# power.net
KiCad netlist of a schematic drawn in Altium Designer
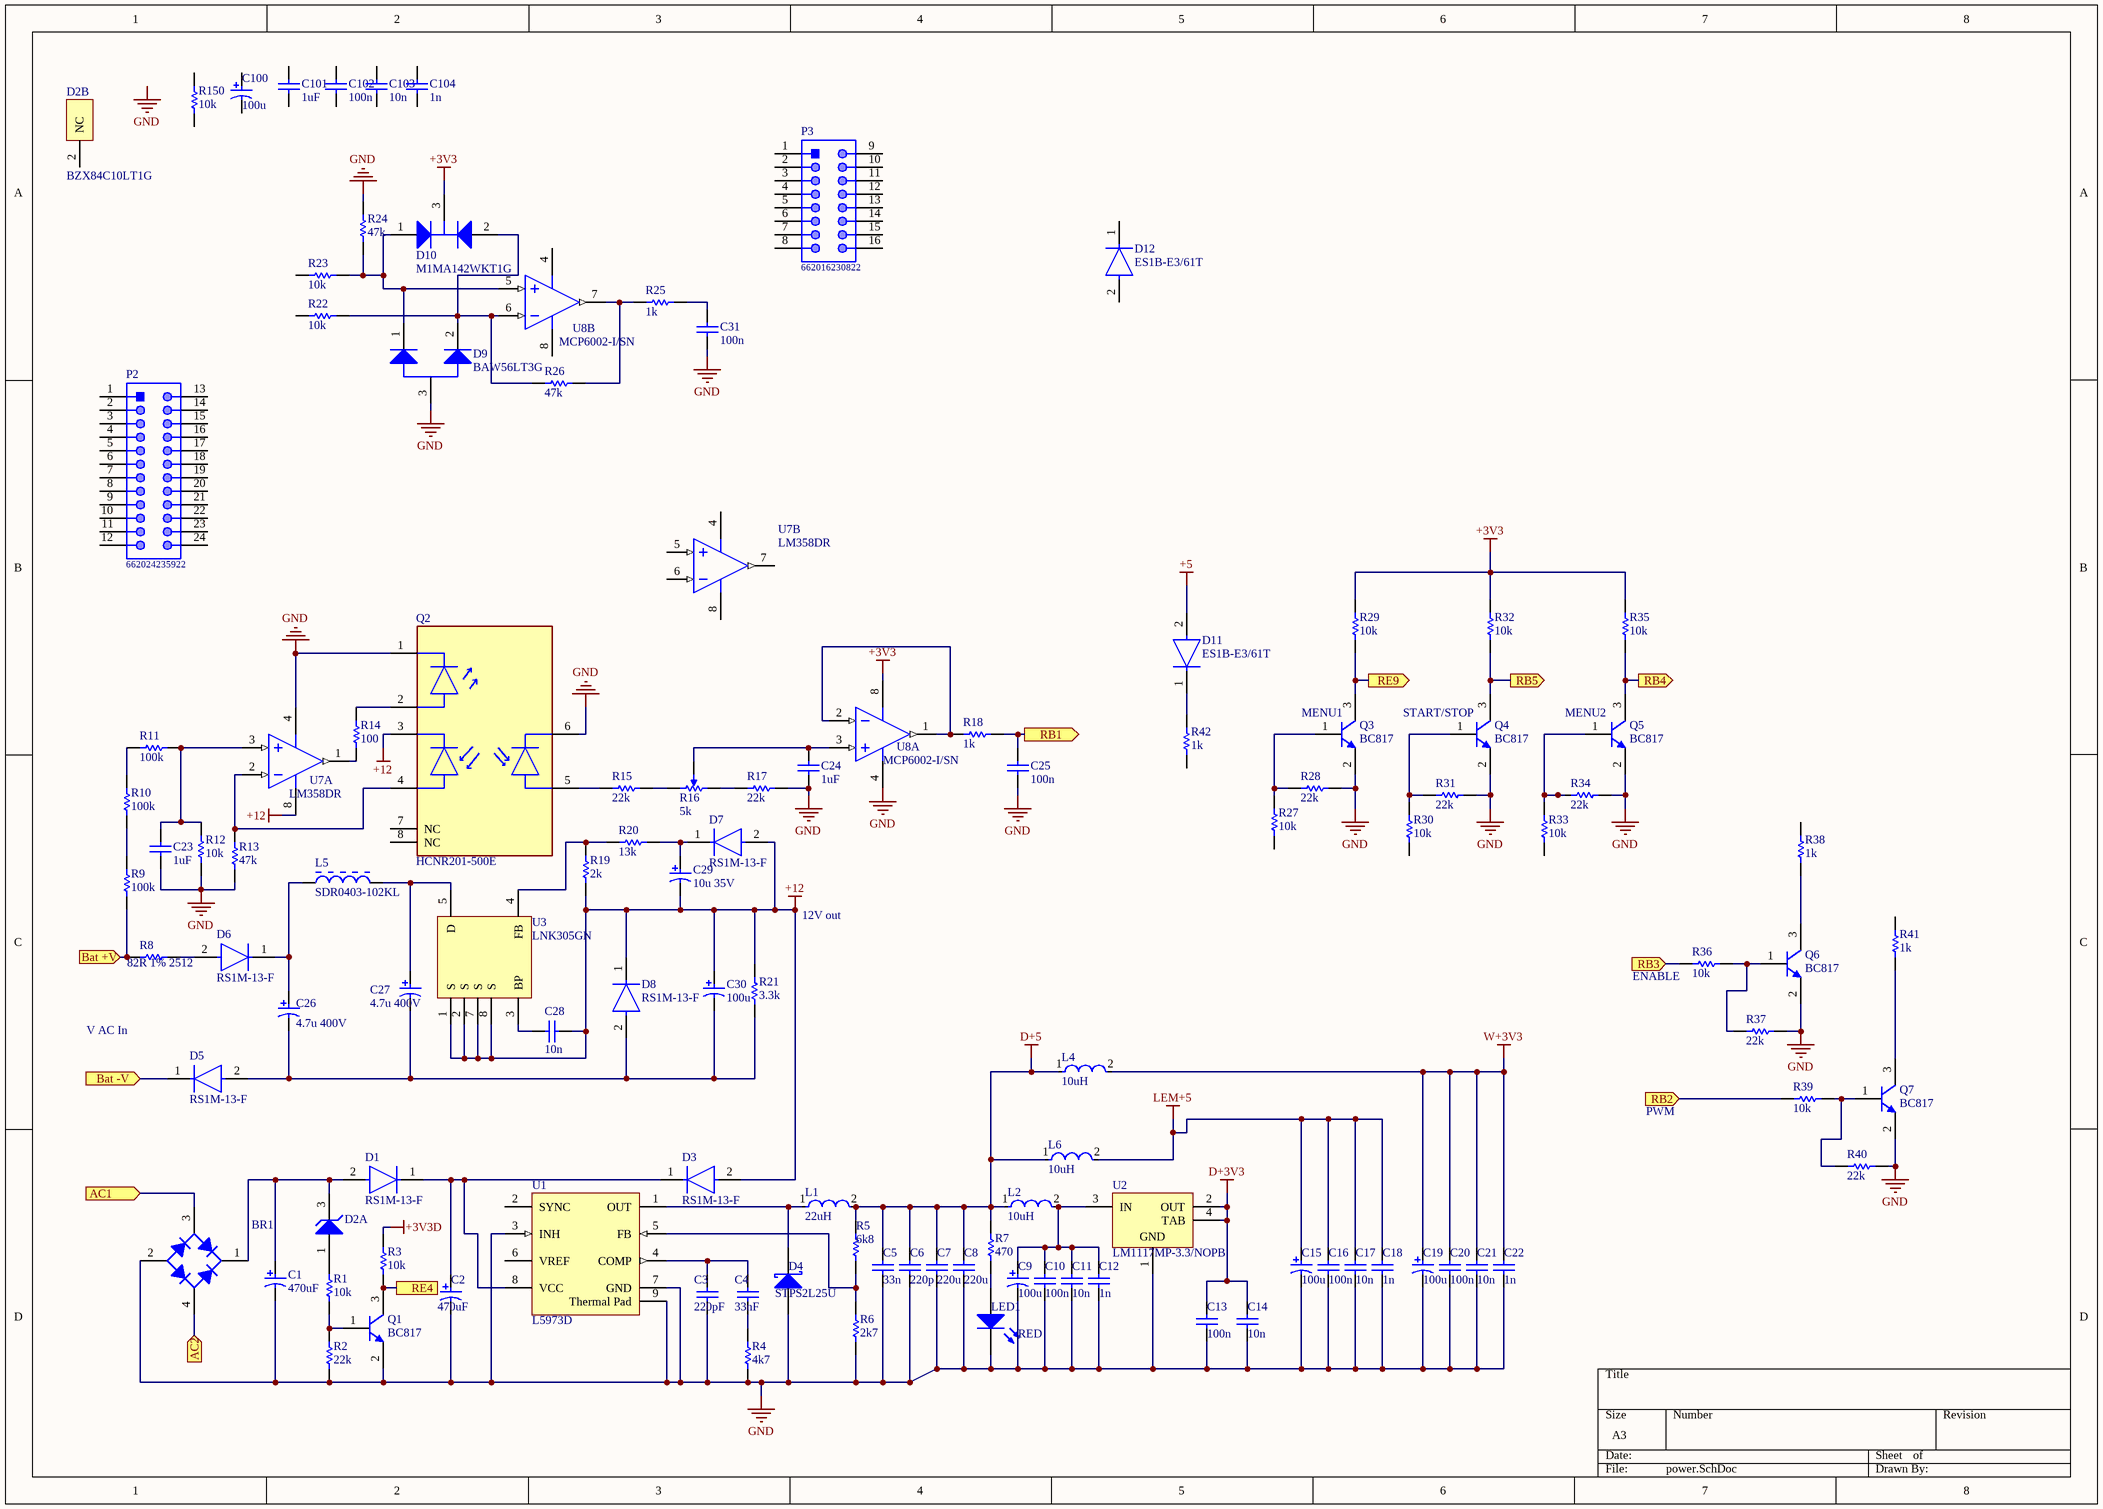
[diagram p0: power.SchDoc]

(export (version "E")
  (design (tool "Eeschema 10.0.6"))
  (components
    (comp (ref "BR1")
      (value "DF10S")
      (footprint "FAIR-SDIP-4_V")
      (description "Bridge Rectifier, 1.5 A, 1000 V, 4-Pin SDIP, RoHS, Tape and Reel")
      (fields (field (name "MANUFACTURER") "FairchildSemiconductor"))
      (libsource (lib "Altium Content Vault") (part "D-KACC-4"))
    )
    (comp (ref "C1")
      (value "470uF")
      (footprint "PNSC-EEV-FK1J471M_L")
      (fields (field (name "MANUFACTURER") "Panasonic"))
      (libsource (lib "Altium Content Vault") (part "CAP-P-2"))
    )
    (comp (ref "C2")
      (value "470uF")
      (footprint "PNSC-EEV-FK1J471M_L")
      (fields (field (name "MANUFACTURER") "Panasonic"))
      (libsource (lib "Altium Content Vault") (part "CAP-P-2"))
    )
    (comp (ref "C3")
      (value "220pF")
      (footprint "CAPC2013X140X50ML20T25")
      (fields
        (field (name "MANUFACTURER") "AVX Interconnect / Elco")
        (field (name "PART NUMBER") "08055A221JAT2A")
      )
      (libsource (lib "Altium Content Vault") (part "CAP"))
    )
    (comp (ref "C4")
      (value "33nF")
      (footprint "CAPC0805(2012)100_L")
      (description "CAP 33nF 50V ±5% 0805 (2012 Metric) Thickness 1mm SMD")
      (fields (field (name "TOLERANCE") "Â±5%"))
      (libsource (lib "Altium Content Vault") (part "CAP"))
    )
    (comp (ref "C5")
      (value "33n")
      (footprint "CAPC0805(2012)100_L")
      (description "CAP 33nF 50V ±5% 0805 (2012 Metric) Thickness 1mm SMD")
      (fields (field (name "TOLERANCE") "Â±5%"))
      (libsource (lib "Altium Content Vault") (part "CAP"))
    )
    (comp (ref "C6")
      (value "220p")
      (footprint "CAPC2013X140X50ML20T25")
      (fields
        (field (name "MANUFACTURER") "AVX Interconnect / Elco")
        (field (name "PART NUMBER") "08055A221JAT2A")
      )
      (libsource (lib "Altium Content Vault") (part "CAP"))
    )
    (comp (ref "C7")
      (value "220u")
      (footprint "CAPC2013X120X55NL10T10")
      (fields (field (name "PART NUMBER") "T488R227M004AAE2K0") (field (name "MANUFACTURER") "Kemet"))
      (libsource (lib "Altium Content Vault") (part "CAP"))
    )
    (comp (ref "C8")
      (value "220u")
      (footprint "CAPC2013X120X55NL10T10")
      (fields (field (name "PART NUMBER") "T488R227M004AAE2K0") (field (name "MANUFACTURER") "Kemet"))
      (libsource (lib "Altium Content Vault") (part "CAP"))
    )
    (comp (ref "C9")
      (value "100u")
      (footprint "KEMT-T495-D_L")
      (description "Capacitor, Tantalum, 100 uF, +/- 10%, 16 V, -55 to 125 degC, 2-Pin SMD, RoHS, Tape and Reel")
      (fields (field (name "MANUFACTURER") "Kemet") (field (name "VOLTAGE") "16VDC"))
      (libsource (lib "Altium Content Vault") (part "CAP-P-2"))
    )
    (comp (ref "C10")
      (value "100n")
      (footprint "CAPC2013X88X50NL20T25")
      (fields (field (name "PART NUMBER") "C0805C104K5RACTU") (field (name "MANUFACTURER") "Kemet"))
      (libsource (lib "Altium Content Vault") (part "CAP"))
    )
    (comp (ref "C11")
      (value "10n")
      (footprint "CAPC2013X140X50LL20T25")
      (fields
        (field (name "PART NUMBER") "08055F103KAT2A")
        (field (name "MANUFACTURER") "AVX Interconnect / Elco")
      )
      (libsource (lib "Altium Content Vault") (part "CAP"))
    )
    (comp (ref "C12")
      (value "1n")
      (footprint "CAPC0805(2012)145_L")
      (description "CAP 1nF 50V ±10% 0805 (2012 Metric) Thickness 1.45mm SMD")
      (fields (field (name "TOLERANCE") "Â±10%"))
      (libsource (lib "Altium Content Vault") (part "CAP"))
    )
    (comp (ref "C13")
      (value "100n")
      (footprint "CAPC2013X88X50NL20T25")
      (fields (field (name "PART NUMBER") "C0805C104K5RACTU") (field (name "MANUFACTURER") "Kemet"))
      (libsource (lib "Altium Content Vault") (part "CAP"))
    )
    (comp (ref "C14")
      (value "10n")
      (footprint "CAPC2013X140X50LL20T25")
      (fields
        (field (name "PART NUMBER") "08055F103KAT2A")
        (field (name "MANUFACTURER") "AVX Interconnect / Elco")
      )
      (libsource (lib "Altium Content Vault") (part "CAP"))
    )
    (comp (ref "C15")
      (value "100u")
      (footprint "KEMT-T495-D_L")
      (description "Capacitor, Tantalum, 100 uF, +/- 10%, 16 V, -55 to 125 degC, 2-Pin SMD, RoHS, Tape and Reel")
      (fields (field (name "MANUFACTURER") "Kemet") (field (name "VOLTAGE") "16VDC"))
      (libsource (lib "Altium Content Vault") (part "CAP-P-2"))
    )
    (comp (ref "C16")
      (value "100n")
      (footprint "CAPC2013X88X50NL20T25")
      (fields (field (name "PART NUMBER") "C0805C104K5RACTU") (field (name "MANUFACTURER") "Kemet"))
      (libsource (lib "Altium Content Vault") (part "CAP"))
    )
    (comp (ref "C17")
      (value "10n")
      (footprint "CAPC2013X140X50LL20T25")
      (fields
        (field (name "PART NUMBER") "08055F103KAT2A")
        (field (name "MANUFACTURER") "AVX Interconnect / Elco")
      )
      (libsource (lib "Altium Content Vault") (part "CAP"))
    )
    (comp (ref "C18")
      (value "1n")
      (footprint "CAPC0805(2012)145_L")
      (description "CAP 1nF 50V ±10% 0805 (2012 Metric) Thickness 1.45mm SMD")
      (fields (field (name "TOLERANCE") "Â±10%"))
      (libsource (lib "Altium Content Vault") (part "CAP"))
    )
    (comp (ref "C19")
      (value "100u")
      (footprint "KEMT-T495-D_L")
      (description "Capacitor, Tantalum, 100 uF, +/- 10%, 16 V, -55 to 125 degC, 2-Pin SMD, RoHS, Tape and Reel")
      (fields (field (name "MANUFACTURER") "Kemet") (field (name "VOLTAGE") "16VDC"))
      (libsource (lib "Altium Content Vault") (part "CAP-P-2"))
    )
    (comp (ref "C20")
      (value "100n")
      (footprint "CAPC2013X88X50NL20T25")
      (fields (field (name "PART NUMBER") "C0805C104K5RACTU") (field (name "MANUFACTURER") "Kemet"))
      (libsource (lib "Altium Content Vault") (part "CAP"))
    )
    (comp (ref "C21")
      (value "10n")
      (footprint "CAPC2013X140X50LL20T25")
      (fields
        (field (name "PART NUMBER") "08055F103KAT2A")
        (field (name "MANUFACTURER") "AVX Interconnect / Elco")
      )
      (libsource (lib "Altium Content Vault") (part "CAP"))
    )
    (comp (ref "C22")
      (value "1n")
      (footprint "CAPC0805(2012)145_L")
      (description "CAP 1nF 50V ±10% 0805 (2012 Metric) Thickness 1.45mm SMD")
      (fields (field (name "TOLERANCE") "Â±10%"))
      (libsource (lib "Altium Content Vault") (part "CAP"))
    )
    (comp (ref "C23")
      (value "1uF")
      (footprint "CAPC0805(2012)145_L")
      (description "CAP 1uF 50V ±10% 0805 (2012 Metric) Thickness 1.45mm SMD")
      (fields (field (name "TOLERANCE") "Â±10%"))
      (libsource (lib "Altium Content Vault") (part "CAP"))
    )
    (comp (ref "C24")
      (value "1uF")
      (footprint "CAPC0805(2012)145_L")
      (description "CAP 1uF 50V ±10% 0805 (2012 Metric) Thickness 1.45mm SMD")
      (fields (field (name "TOLERANCE") "Â±10%"))
      (libsource (lib "Altium Content Vault") (part "CAP"))
    )
    (comp (ref "C25")
      (value "100n")
      (footprint "CAPC2013X88X50NL20T25")
      (fields (field (name "PART NUMBER") "C0805C104K5RACTU") (field (name "MANUFACTURER") "Kemet"))
      (libsource (lib "Altium Content Vault") (part "CAP"))
    )
    (comp (ref "C26")
      (value "4.7u 400V")
      (footprint "NIC-ULR-8x10-2_V")
      (fields (field (name "PARTNUMBER") "ULR2G4R7MNL1GS") (field (name "MANUFACTURER") "Nichicon"))
      (libsource (lib "Altium Content Vault") (part "NIC-CAP-P-2"))
    )
    (comp (ref "C27")
      (value "4.7u 400V")
      (footprint "NIC-ULR-8x10-2_V")
      (fields (field (name "PARTNUMBER") "ULR2G4R7MNL1GS") (field (name "MANUFACTURER") "Nichicon"))
      (libsource (lib "Altium Content Vault") (part "NIC-CAP-P-2"))
    )
    (comp (ref "C28")
      (value "10n")
      (footprint "CAPC2013X140X50LL20T25")
      (fields
        (field (name "PART NUMBER") "08055F103KAT2A")
        (field (name "MANUFACTURER") "AVX Interconnect / Elco")
      )
      (libsource (lib "Altium Content Vault") (part "CAP"))
    )
    (comp (ref "C29")
      (value "10u 35V")
      (footprint "KEMT-T491-D_L")
      (description "Tantalum Capacitor, 10 uF, +/- 10%, 35 V, -55 to 125 degC, 2-Pin SMD, RoHS, Tape and Reel")
      (fields (field (name "MANUFACTURER") "Kemet") (field (name "TOLERANCE") "20%"))
      (libsource (lib "Altium Content Vault") (part "CAP-P-2"))
    )
    (comp (ref "C30")
      (value "100u")
      (footprint "KEMT-T491-D_L")
      (fields
        (field (name "MANUFACTURER") "Kemet")
        (field (name "VOLTAGE") "16V")
        (field (name "TOLERANCE") "10%")
      )
      (libsource (lib "Altium Content Vault") (part "CAP-P-2"))
    )
    (comp (ref "C31")
      (value "100n")
      (footprint "CAPC2013X88X50NL20T25")
      (fields (field (name "PART NUMBER") "C0805C104K5RACTU") (field (name "MANUFACTURER") "Kemet"))
      (libsource (lib "Altium Content Vault") (part "CAP"))
    )
    (comp (ref "C100")
      (value "100u")
      (footprint "KEMT-T495-D_L")
      (description "Capacitor, Tantalum, 100 uF, +/- 10%, 16 V, -55 to 125 degC, 2-Pin SMD, RoHS, Tape and Reel")
      (fields (field (name "MANUFACTURER") "Kemet") (field (name "VOLTAGE") "16VDC"))
      (libsource (lib "Altium Content Vault") (part "CAP-P-2"))
    )
    (comp (ref "C101")
      (value "1uF")
      (footprint "CAPC0805(2012)145_L")
      (description "CAP 1uF 50V ±10% 0805 (2012 Metric) Thickness 1.45mm SMD")
      (fields (field (name "TOLERANCE") "Â±10%"))
      (libsource (lib "Altium Content Vault") (part "CAP"))
    )
    (comp (ref "C102")
      (value "100n")
      (footprint "CAPC2013X88X50NL20T25")
      (fields (field (name "PART NUMBER") "C0805C104K5RACTU") (field (name "MANUFACTURER") "Kemet"))
      (libsource (lib "Altium Content Vault") (part "CAP"))
    )
    (comp (ref "C103")
      (value "10n")
      (footprint "CAPC2013X140X50LL20T25")
      (fields
        (field (name "PART NUMBER") "08055F103KAT2A")
        (field (name "MANUFACTURER") "AVX Interconnect / Elco")
      )
      (libsource (lib "Altium Content Vault") (part "CAP"))
    )
    (comp (ref "C104")
      (value "1n")
      (footprint "CAPC0805(2012)145_L")
      (description "CAP 1nF 50V ±10% 0805 (2012 Metric) Thickness 1.45mm SMD")
      (fields (field (name "TOLERANCE") "Â±10%"))
      (libsource (lib "Altium Content Vault") (part "CAP"))
    )
    (comp (ref "D1")
      (value "RS1M-13-F")
      (footprint "FP-SMA-MFG")
      (description "DIODE GEN PURP 1KV 1A SMA")
      (fields
        (field (name "MANUFACTURER") "Diodes Inc.")
        (field (name "OCTOPART") "https://octopart.com/rs1m-13-f-diodes+inc.-333072")
      )
      (libsource (lib "Altium Content Vault") (part "d7152d700b627762746794eb795d46e"))
    )
    (comp (ref "D2")
      (value "BZX84C10LT1G")
      (footprint "ONSC-SOT-23-3-318-08_V")
      (description "Zener Voltage Regulator, 225 mW, 3-Pin SOT-23, Pb-Free, Tape and Reel")
      (fields (field (name "MANUFACTURER") "On Semiconductor"))
      (libsource (lib "Altium Content Vault") (part "ONSC-A1K3-3"))
    )
    (comp (ref "D3")
      (value "RS1M-13-F")
      (footprint "FP-SMA-MFG")
      (description "DIODE GEN PURP 1KV 1A SMA")
      (fields
        (field (name "MANUFACTURER") "Diodes Inc.")
        (field (name "OCTOPART") "https://octopart.com/rs1m-13-f-diodes+inc.-333072")
      )
      (libsource (lib "Altium Content Vault") (part "d7152d700b627762746794eb795d46e"))
    )
    (comp (ref "D4")
      (value "STPS2L25U")
      (footprint "STM-SMB_P_V")
      (description "Low Drop Power Schottky Rectifier, 2 A, 25 V, 2-Pin SMD (SMB), RoHS, Tape and Reel")
      (fields (field (name "MANUFACTURER") "STMicroelectronics"))
      (libsource (lib "Altium Content Vault") (part "DSKY-AK-2"))
    )
    (comp (ref "D5")
      (value "RS1M-13-F")
      (footprint "FP-SMA-MFG")
      (description "DIODE GEN PURP 1KV 1A SMA")
      (fields
        (field (name "MANUFACTURER") "Diodes Inc.")
        (field (name "OCTOPART") "https://octopart.com/rs1m-13-f-diodes+inc.-333072")
      )
      (libsource (lib "Altium Content Vault") (part "d7152d700b627762746794eb795d46e"))
    )
    (comp (ref "D6")
      (value "RS1M-13-F")
      (footprint "FP-SMA-MFG")
      (description "DIODE GEN PURP 1KV 1A SMA")
      (fields
        (field (name "MANUFACTURER") "Diodes Inc.")
        (field (name "OCTOPART") "https://octopart.com/rs1m-13-f-diodes+inc.-333072")
      )
      (libsource (lib "Altium Content Vault") (part "d7152d700b627762746794eb795d46e"))
    )
    (comp (ref "D7")
      (value "RS1M-13-F")
      (footprint "FP-SMA-MFG")
      (description "DIODE GEN PURP 1KV 1A SMA")
      (fields
        (field (name "MANUFACTURER") "Diodes Inc.")
        (field (name "OCTOPART") "https://octopart.com/rs1m-13-f-diodes+inc.-333072")
      )
      (libsource (lib "Altium Content Vault") (part "d7152d700b627762746794eb795d46e"))
    )
    (comp (ref "D8")
      (value "RS1M-13-F")
      (footprint "FP-SMA-MFG")
      (description "DIODE GEN PURP 1KV 1A SMA")
      (fields
        (field (name "MANUFACTURER") "Diodes Inc.")
        (field (name "OCTOPART") "https://octopart.com/rs1m-13-f-diodes+inc.-333072")
      )
      (libsource (lib "Altium Content Vault") (part "d7152d700b627762746794eb795d46e"))
    )
    (comp (ref "D9")
      (value "BAW56LT3G")
      (footprint "ONSC-SOT-23-3-318-08_V")
      (description "Dual Switching Diodes, Common Anode, 3-Pin SOT-23, Pb-Free, Tape and Reel")
      (fields (field (name "MANUFACTURER") "On Semiconductor"))
      (libsource (lib "Altium Content Vault") (part "ONSC-D-K1K2A3-3"))
    )
    (comp (ref "D10")
      (value "M1MA142WKT1G")
      (footprint "ONSC-SOT-323-3-419-04_V")
      (description "Common Cathode Silicon Dual Switching Diodes, 3-Pin SOT-323, Pb-Free, Tape and Reel")
      (fields (field (name "MANUFACTURER") "On Semiconductor"))
      (libsource (lib "Altium Content Vault") (part "ONSC-D-A1A2K3-3"))
    )
    (comp (ref "D11")
      (value "ES1B-E3/61T")
      (footprint "FP-95400-MFG")
      (description "DIODE GEN PURP 100V 1A DO214AC")
      (fields
        (field (name "OCTOPART") "https://octopart.com/es1b-e3%2F61t-vishay-39550258")
        (field (name "MANUFACTURER") "Vishay")
      )
      (libsource (lib "Altium Content Vault") (part "d7152d700b627762746794eb795d46e"))
    )
    (comp (ref "D12")
      (value "ES1B-E3/61T")
      (footprint "FP-95400-MFG")
      (description "DIODE GEN PURP 100V 1A DO214AC")
      (fields
        (field (name "OCTOPART") "https://octopart.com/es1b-e3%2F61t-vishay-39550258")
        (field (name "MANUFACTURER") "Vishay")
      )
      (libsource (lib "Altium Content Vault") (part "d7152d700b627762746794eb795d46e"))
    )
    (comp (ref "L1")
      (value "22uH")
      (footprint "FP-IHLP-2525CZ-FP_2_413x3-MFG")
      (description "Commercial Inductors, Low DCR Series 22uH 2.9A 135mΩ 20%")
      (fields (field (name "TOLERANCE") "20%"))
      (libsource (lib "Altium Content Vault") (part "725321dda6339637d4d059423bc1c3c"))
    )
    (comp (ref "L2")
      (value "10uH")
      (footprint "FP-IHLP-2020BZ-FP_1_905x2-MFG")
      (description "Fixed Inductors Commercial High Saturation Series 10uH 2.3A 199mΩ 20%")
      (fields (field (name "TOLERANCE") "20%"))
      (libsource (lib "Altium Content Vault") (part "725321dda6339637d4d059423bc1c3c"))
    )
    (comp (ref "L4")
      (value "10uH")
      (footprint "FP-IHLP-2020BZ-FP_1_905x2-MFG")
      (description "Fixed Inductors Commercial High Saturation Series 10uH 2.3A 199mΩ 20%")
      (fields (field (name "TOLERANCE") "20%"))
      (libsource (lib "Altium Content Vault") (part "725321dda6339637d4d059423bc1c3c"))
    )
    (comp (ref "L5")
      (value "SDR0403-102KL")
      (footprint "BOUR-SDR0403-2_V")
      (fields (field (name "MANUFACTURER") "Bourns"))
      (libsource (lib "Altium Content Vault") (part "BOUR-IND-2A"))
    )
    (comp (ref "L6")
      (value "10uH")
      (footprint "FP-IHLP-2020BZ-FP_1_905x2-MFG")
      (description "Fixed Inductors Commercial High Saturation Series 10uH 2.3A 199mΩ 20%")
      (fields (field (name "TOLERANCE") "20%"))
      (libsource (lib "Altium Content Vault") (part "725321dda6339637d4d059423bc1c3c"))
    )
    (comp (ref "LED1")
      (value "RED")
      (footprint "0603_A")
      (description "SMD mono-color Chip LED, WL-SMCW, Red")
      (fields (field (name "MANUFACTURER") "Wuerth Elektronik") (field (name "PARTNUMBER") "150060RS75000"))
      (libsource (lib "Altium Content Vault") (part "WE-LED_K1A2-2"))
    )
    (comp (ref "P2")
      (value "662024235922")
      (footprint "662024235922")
      (description "SMT Male Header WR-MPC3, with THT Retention Clips, Vertical, Dual Row, pitch 3 mm, 24 pins")
      (fields (field (name "MANUFACTURER") "Wurth Elektronik") (field (name "PUBLISHER") "WurthElektronik"))
      (libsource (lib "Altium Content Vault") (part "WE-CN-2P-M-R24_A"))
    )
    (comp (ref "P3")
      (value "662016230822")
      (footprint "662016230822")
      (description "SMT Male Header WR-MPC3, with THT Rention Clips, Right Angled, Dual Row, pitch 3 mm, 16 pins")
      (fields (field (name "MANUFACTURER") "Wurth Elektronik") (field (name "PUBLISHER") "WurthElektronik"))
      (libsource (lib "Altium Content Vault") (part "WE-CN-2P-M-R16_A"))
    )
    (comp (ref "Q1")
      (value "BC817")
      (footprint "ONSC-SOT-23-3-318-08_V")
      (description "General Purpose Transistor, NPN Silicon, 3-Pin SOT-23, Pb-Free, Tape and Reel")
      (fields (field (name "PARTNUMBER") "BC817-16LT1G") (field (name "MANUFACTURER") "On Semiconductor"))
      (libsource (lib "Altium Content Vault") (part "ONSC-NPN-B1E2C3-3"))
    )
    (comp (ref "Q2")
      (value "HCNR201-500E")
      (footprint "FP-HCNR201-500E-MFG")
      (description "OPTOISO 5KV LINEAR PHVOLT 8DIPGW")
      (fields
        (field (name "MANUFACTURER") "Broadcom")
        (field (name "OCTOPART") "https://octopart.com/hcnr201-500e-broadcom-71127631")
      )
      (libsource (lib "Altium Content Vault") (part "a9ac1b52e7cb99e198fa14094656dec"))
    )
    (comp (ref "Q3")
      (value "BC817")
      (footprint "ONSC-SOT-23-3-318-08_V")
      (description "General Purpose Transistor, NPN Silicon, 3-Pin SOT-23, Pb-Free, Tape and Reel")
      (fields (field (name "PARTNUMBER") "BC817-16LT1G") (field (name "MANUFACTURER") "On Semiconductor"))
      (libsource (lib "Altium Content Vault") (part "ONSC-NPN-B1E2C3-3"))
    )
    (comp (ref "Q4")
      (value "BC817")
      (footprint "ONSC-SOT-23-3-318-08_V")
      (description "General Purpose Transistor, NPN Silicon, 3-Pin SOT-23, Pb-Free, Tape and Reel")
      (fields (field (name "PARTNUMBER") "BC817-16LT1G") (field (name "MANUFACTURER") "On Semiconductor"))
      (libsource (lib "Altium Content Vault") (part "ONSC-NPN-B1E2C3-3"))
    )
    (comp (ref "Q5")
      (value "BC817")
      (footprint "ONSC-SOT-23-3-318-08_V")
      (description "General Purpose Transistor, NPN Silicon, 3-Pin SOT-23, Pb-Free, Tape and Reel")
      (fields (field (name "PARTNUMBER") "BC817-16LT1G") (field (name "MANUFACTURER") "On Semiconductor"))
      (libsource (lib "Altium Content Vault") (part "ONSC-NPN-B1E2C3-3"))
    )
    (comp (ref "Q6")
      (value "BC817")
      (footprint "ONSC-SOT-23-3-318-08_V")
      (description "General Purpose Transistor, NPN Silicon, 3-Pin SOT-23, Pb-Free, Tape and Reel")
      (fields (field (name "PARTNUMBER") "BC817-16LT1G") (field (name "MANUFACTURER") "On Semiconductor"))
      (libsource (lib "Altium Content Vault") (part "ONSC-NPN-B1E2C3-3"))
    )
    (comp (ref "Q7")
      (value "BC817")
      (footprint "ONSC-SOT-23-3-318-08_V")
      (description "General Purpose Transistor, NPN Silicon, 3-Pin SOT-23, Pb-Free, Tape and Reel")
      (fields (field (name "PARTNUMBER") "BC817-16LT1G") (field (name "MANUFACTURER") "On Semiconductor"))
      (libsource (lib "Altium Content Vault") (part "ONSC-NPN-B1E2C3-3"))
    )
    (comp (ref "R1")
      (value "10k")
      (footprint "RESC2013X70X40LL20T20")
      (fields (field (name "MANUFACTURER") "Panasonic") (field (name "PART NUMBER") "ERJ-6ENF1002V"))
      (libsource (lib "Altium Content Vault") (part "RES"))
    )
    (comp (ref "R2")
      (value "22k")
      (footprint "RESC2013X70X40NL20T20")
      (fields (field (name "PART NUMBER") "ERJ6ENF2202V") (field (name "MANUFACTURER") "Panasonic"))
      (libsource (lib "Altium Content Vault") (part "RES"))
    )
    (comp (ref "R3")
      (value "10k")
      (footprint "RESC2013X70X40LL20T20")
      (fields (field (name "MANUFACTURER") "Panasonic") (field (name "PART NUMBER") "ERJ-6ENF1002V"))
      (libsource (lib "Altium Content Vault") (part "RES"))
    )
    (comp (ref "R4")
      (value "4k7")
      (footprint "RESC2013X70X40LL20T20")
      (fields (field (name "PART NUMBER") "ERJ6ENF4701V") (field (name "MANUFACTURER") "Panasonic"))
      (libsource (lib "Altium Content Vault") (part "RES"))
    )
    (comp (ref "R5")
      (value "6k8")
      (footprint "RESC2013X70X40LL20T20")
      (fields (field (name "MANUFACTURER") "Panasonic") (field (name "PART NUMBER") "ERJ6ENF6801V"))
      (libsource (lib "Altium Content Vault") (part "RES"))
    )
    (comp (ref "R6")
      (value "2k7")
      (footprint "RESC2013X70X40NL20T20")
      (fields (field (name "MANUFACTURER") "Panasonic") (field (name "PART NUMBER") "ERJ6ENF2701V"))
      (libsource (lib "Altium Content Vault") (part "RES"))
    )
    (comp (ref "R7")
      (value "470")
      (footprint "RESC2013X70X40ML20T20")
      (description "Chip Resistor, 470 Ohm, +/- 1%, 0.125 W, -55 to 155 degC, 0805 (2012 Metric), RoHS, Tape and Reel")
      (fields (field (name "MANUFACTURER") "Panasonic"))
      (libsource (lib "Altium Content Vault") (part "RES-2"))
    )
    (comp (ref "R8")
      (value "82R 1% 2512")
      (footprint "RESC2512(6432)_N")
      (description "82R 1W 1% 2512 (6432 Metric)  SMD")
      (fields (field (name "TOLERANCE") "1 %") (field (name "POWER") "1 W"))
      (libsource (lib "Altium Content Vault") (part "RES"))
    )
    (comp (ref "R9")
      (value "100k")
      (footprint "RESC2013X70X40ML20T20")
      (fields (field (name "PART NUMBER") "ERJ-6ENF1003V") (field (name "MANUFACTURER") "Panasonic"))
      (libsource (lib "Altium Content Vault") (part "RES"))
    )
    (comp (ref "R10")
      (value "100k")
      (footprint "RESC2013X70X40ML20T20")
      (fields (field (name "PART NUMBER") "ERJ-6ENF1003V") (field (name "MANUFACTURER") "Panasonic"))
      (libsource (lib "Altium Content Vault") (part "RES"))
    )
    (comp (ref "R11")
      (value "100k")
      (footprint "RESC2013X70X40ML20T20")
      (fields (field (name "PART NUMBER") "ERJ-6ENF1003V") (field (name "MANUFACTURER") "Panasonic"))
      (libsource (lib "Altium Content Vault") (part "RES"))
    )
    (comp (ref "R12")
      (value "10k")
      (footprint "RESC2013X70X40ML20T20")
      (fields (field (name "MANUFACTURER") "Panasonic") (field (name "PART NUMBER") "ERJ-6ENF1002V"))
      (libsource (lib "Altium Content Vault") (part "RES"))
    )
    (comp (ref "R13")
      (value "47k")
      (footprint "RESC2013X70X40ML20T20")
      (fields (field (name "MANUFACTURER") "Panasonic") (field (name "PART NUMBER") "ERJ6ENF4702V"))
      (libsource (lib "Altium Content Vault") (part "RES"))
    )
    (comp (ref "R14")
      (value "100")
      (footprint "RESC2013X70X40LL20T20")
      (fields (field (name "MANUFACTURER") "Panasonic") (field (name "PART NUMBER") "ERJ-6ENF1000V"))
      (libsource (lib "Altium Content Vault") (part "RES"))
    )
    (comp (ref "R15")
      (value "22k")
      (footprint "RESC2013X70X40NL20T20")
      (fields (field (name "PART NUMBER") "ERJ6ENF2202V") (field (name "MANUFACTURER") "Panasonic"))
      (libsource (lib "Altium Content Vault") (part "RES"))
    )
    (comp (ref "R16")
      (value "5k")
      (footprint "BOUR-3314J-1_V")
      (fields
        (field (name "POWER") "250")
        (field (name "MANUFACTURER") "Bourns")
        (field (name "TOLERANCE") "±20%")
      )
      (libsource (lib "Altium Content Vault") (part "RES-ADJ-3_A"))
    )
    (comp (ref "R17")
      (value "22k")
      (footprint "RESC2013X70X40NL20T20")
      (fields (field (name "PART NUMBER") "ERJ6ENF2202V") (field (name "MANUFACTURER") "Panasonic"))
      (libsource (lib "Altium Content Vault") (part "RES"))
    )
    (comp (ref "R18")
      (value "1k")
      (footprint "RESC2013X70X40ML20T20")
      (description "Chip Resistor, 1 KOhm, +/- 1%, 0.125 W, -55 to 155 degC, 0805 (2012 Metric), RoHS, Tape and Reel")
      (fields (field (name "MANUFACTURER") "Panasonic"))
      (libsource (lib "Altium Content Vault") (part "RES-2"))
    )
    (comp (ref "R19")
      (value "2k")
      (footprint "RESC2013X70X40NL20T20")
      (fields (field (name "MANUFACTURER") "Panasonic") (field (name "PART NUMBER") "ERJ-6ENF2001V"))
      (libsource (lib "Altium Content Vault") (part "RES"))
    )
    (comp (ref "R20")
      (value "13k")
      (footprint "RESC2013X70X40NL20T20")
      (fields (field (name "PART NUMBER") "ERJ-6ENF1302V") (field (name "MANUFACTURER") "Panasonic"))
      (libsource (lib "Altium Content Vault") (part "RES"))
    )
    (comp (ref "R21")
      (value "3.3k")
      (footprint "RESC2013X70X40LL20T20")
      (fields (field (name "MANUFACTURER") "Panasonic") (field (name "PART NUMBER") "ERJ6ENF3301V"))
      (libsource (lib "Altium Content Vault") (part "RES"))
    )
    (comp (ref "R22")
      (value "10k")
      (footprint "RESC2013X70X40ML20T20")
      (fields (field (name "MANUFACTURER") "Panasonic") (field (name "PART NUMBER") "ERJ-6ENF1002V"))
      (libsource (lib "Altium Content Vault") (part "RES"))
    )
    (comp (ref "R23")
      (value "10k")
      (footprint "RESC2013X70X40ML20T20")
      (fields (field (name "MANUFACTURER") "Panasonic") (field (name "PART NUMBER") "ERJ-6ENF1002V"))
      (libsource (lib "Altium Content Vault") (part "RES"))
    )
    (comp (ref "R24")
      (value "47k")
      (footprint "RESC2013X70X40ML20T20")
      (fields (field (name "MANUFACTURER") "Panasonic") (field (name "PART NUMBER") "ERJ6ENF4702V"))
      (libsource (lib "Altium Content Vault") (part "RES"))
    )
    (comp (ref "R25")
      (value "1k")
      (footprint "RESC2013X70X40ML20T20")
      (description "Chip Resistor, 1 KOhm, +/- 1%, 0.125 W, -55 to 155 degC, 0805 (2012 Metric), RoHS, Tape and Reel")
      (fields (field (name "MANUFACTURER") "Panasonic"))
      (libsource (lib "Altium Content Vault") (part "RES-2"))
    )
    (comp (ref "R26")
      (value "47k")
      (footprint "RESC2013X70X40ML20T20")
      (fields (field (name "MANUFACTURER") "Panasonic") (field (name "PART NUMBER") "ERJ6ENF4702V"))
      (libsource (lib "Altium Content Vault") (part "RES"))
    )
    (comp (ref "R27")
      (value "10k")
      (footprint "RESC2013X70X40ML20T20")
      (fields (field (name "MANUFACTURER") "Panasonic") (field (name "PART NUMBER") "ERJ-6ENF1002V"))
      (libsource (lib "Altium Content Vault") (part "RES"))
    )
    (comp (ref "R28")
      (value "22k")
      (footprint "RESC2013X70X40NL20T20")
      (fields (field (name "PART NUMBER") "ERJ6ENF2202V") (field (name "MANUFACTURER") "Panasonic"))
      (libsource (lib "Altium Content Vault") (part "RES"))
    )
    (comp (ref "R29")
      (value "10k")
      (footprint "RESC2013X70X40ML20T20")
      (fields (field (name "MANUFACTURER") "Panasonic") (field (name "PART NUMBER") "ERJ-6ENF1002V"))
      (libsource (lib "Altium Content Vault") (part "RES"))
    )
    (comp (ref "R30")
      (value "10k")
      (footprint "RESC2013X70X40ML20T20")
      (fields (field (name "MANUFACTURER") "Panasonic") (field (name "PART NUMBER") "ERJ-6ENF1002V"))
      (libsource (lib "Altium Content Vault") (part "RES"))
    )
    (comp (ref "R31")
      (value "22k")
      (footprint "RESC2013X70X40NL20T20")
      (fields (field (name "PART NUMBER") "ERJ6ENF2202V") (field (name "MANUFACTURER") "Panasonic"))
      (libsource (lib "Altium Content Vault") (part "RES"))
    )
    (comp (ref "R32")
      (value "10k")
      (footprint "RESC2013X70X40ML20T20")
      (fields (field (name "MANUFACTURER") "Panasonic") (field (name "PART NUMBER") "ERJ-6ENF1002V"))
      (libsource (lib "Altium Content Vault") (part "RES"))
    )
    (comp (ref "R33")
      (value "10k")
      (footprint "RESC2013X70X40ML20T20")
      (fields (field (name "MANUFACTURER") "Panasonic") (field (name "PART NUMBER") "ERJ-6ENF1002V"))
      (libsource (lib "Altium Content Vault") (part "RES"))
    )
    (comp (ref "R34")
      (value "22k")
      (footprint "RESC2013X70X40NL20T20")
      (fields (field (name "PART NUMBER") "ERJ6ENF2202V") (field (name "MANUFACTURER") "Panasonic"))
      (libsource (lib "Altium Content Vault") (part "RES"))
    )
    (comp (ref "R35")
      (value "10k")
      (footprint "RESC2013X70X40ML20T20")
      (fields (field (name "MANUFACTURER") "Panasonic") (field (name "PART NUMBER") "ERJ-6ENF1002V"))
      (libsource (lib "Altium Content Vault") (part "RES"))
    )
    (comp (ref "R36")
      (value "10k")
      (footprint "RESC2013X70X40ML20T20")
      (fields (field (name "MANUFACTURER") "Panasonic") (field (name "PART NUMBER") "ERJ-6ENF1002V"))
      (libsource (lib "Altium Content Vault") (part "RES"))
    )
    (comp (ref "R37")
      (value "22k")
      (footprint "RESC2013X70X40NL20T20")
      (fields (field (name "PART NUMBER") "ERJ6ENF2202V") (field (name "MANUFACTURER") "Panasonic"))
      (libsource (lib "Altium Content Vault") (part "RES"))
    )
    (comp (ref "R38")
      (value "1k")
      (footprint "RESC2013X70X40ML20T20")
      (description "Chip Resistor, 1 KOhm, +/- 1%, 0.125 W, -55 to 155 degC, 0805 (2012 Metric), RoHS, Tape and Reel")
      (fields (field (name "MANUFACTURER") "Panasonic"))
      (libsource (lib "Altium Content Vault") (part "RES-2"))
    )
    (comp (ref "R39")
      (value "10k")
      (footprint "RESC2013X70X40ML20T20")
      (fields (field (name "MANUFACTURER") "Panasonic") (field (name "PART NUMBER") "ERJ-6ENF1002V"))
      (libsource (lib "Altium Content Vault") (part "RES"))
    )
    (comp (ref "R40")
      (value "22k")
      (footprint "RESC2013X70X40NL20T20")
      (fields (field (name "PART NUMBER") "ERJ6ENF2202V") (field (name "MANUFACTURER") "Panasonic"))
      (libsource (lib "Altium Content Vault") (part "RES"))
    )
    (comp (ref "R41")
      (value "1k")
      (footprint "RESC2013X70X40ML20T20")
      (description "Chip Resistor, 1 KOhm, +/- 1%, 0.125 W, -55 to 155 degC, 0805 (2012 Metric), RoHS, Tape and Reel")
      (fields (field (name "MANUFACTURER") "Panasonic"))
      (libsource (lib "Altium Content Vault") (part "RES-2"))
    )
    (comp (ref "R42")
      (value "1k")
      (footprint "RESC2013X70X40ML20T20")
      (description "Chip Resistor, 1 KOhm, +/- 1%, 0.125 W, -55 to 155 degC, 0805 (2012 Metric), RoHS, Tape and Reel")
      (fields (field (name "MANUFACTURER") "Panasonic"))
      (libsource (lib "Altium Content Vault") (part "RES-2"))
    )
    (comp (ref "R150")
      (value "10k")
      (footprint "RESC2013X70X40ML20T20")
      (fields (field (name "MANUFACTURER") "Panasonic") (field (name "PART NUMBER") "ERJ-6ENF1002V"))
      (libsource (lib "Altium Content Vault") (part "RES"))
    )
    (comp (ref "U1")
      (value "L5973D")
      (footprint "HSO-8_L")
      (description "2.5A, Switch step-down switching regulator, 1.235 to 35V, 8-Pin HSOP")
      (libsource (lib "Altium Content Vault") (part "PM-SWREG-L5970-IL9"))
    )
    (comp (ref "U2")
      (value "LM1117MP-3.3/NOPB")
      (footprint "DCY0004A_N")
      (description "800mA Low-Dropout Linear Regulator, 4-pin SOT-223, Pb-Free")
      (fields (field (name "MANUFACTURER") "Texas Instruments"))
      (libsource (lib "Altium Content Vault") (part "PM-REG-LM1086-SOT4"))
    )
    (comp (ref "U3")
      (value "LNK305GN")
      (footprint "PI-SMD-8B-7_V")
      (fields (field (name "MANUFACTURER") "Power Integrations"))
      (libsource (lib "Altium Content Vault") (part "PI-LNK30X-G_P-7"))
    )
    (comp (ref "U7")
      (value "LM358DR")
      (footprint "D0008A_L")
      (libsource (lib "Altium Content Vault") (part "TI-LM358-8"))
    )
    (comp (ref "U8")
      (value "MCP6002-I/SN")
      (footprint "SOIC-SN8_M")
      (description "1 MHz, Low-Power Operational Amplifier, 8-Pin SOIC, Industrial Temperature")
      (libsource (lib "Altium Content Vault") (part "AMP-OPA-MCP6002-IL8"))
    )
  )
  (nets
    (net (code "1") (name "+3V3") (class "Default")
      (node (ref "D10") (pin "3") (pinfunction "K_3") (pintype "passive"))
      (node (ref "R29") (pin "1") (pinfunction "1_1") (pintype "passive"))
      (node (ref "R32") (pin "1") (pinfunction "1_1") (pintype "passive"))
      (node (ref "R35") (pin "1") (pinfunction "1_1") (pintype "passive"))
      (node (ref "U8") (pin "8") (pinfunction "VDD_8") (pintype "power_in"))
    )
    (net (code "2") (name "+3V3D") (class "Default")
      (node (ref "R3") (pin "2") (pinfunction "2_2") (pintype "passive"))
    )
    (net (code "3") (name "+5") (class "Default")
      (node (ref "D11") (pin "2") (pinfunction "A_2") (pintype "passive"))
    )
    (net (code "4") (name "+12") (class "Default")
      (node (ref "C28") (pin "1") (pinfunction "1_1") (pintype "passive"))
      (node (ref "C29") (pin "2") (pinfunction "2_2") (pintype "passive"))
      (node (ref "C30") (pin "1") (pinfunction "1_1") (pintype "passive"))
      (node (ref "D3") (pin "2") (pinfunction "A_2") (pintype "passive"))
      (node (ref "D7") (pin "2") (pinfunction "A_2") (pintype "passive"))
      (node (ref "D8") (pin "1") (pinfunction "C_1") (pintype "passive"))
      (node (ref "Q2") (pin "3") (pinfunction "PD1_CATHODE_3") (pintype "passive"))
      (node (ref "R19") (pin "1") (pinfunction "1_1") (pintype "passive"))
      (node (ref "R21") (pin "2") (pinfunction "2_2") (pintype "passive"))
      (node (ref "U3") (pin "1") (pinfunction "S_1") (pintype "passive"))
      (node (ref "U3") (pin "2") (pinfunction "S_2") (pintype "passive"))
      (node (ref "U3") (pin "7") (pinfunction "S_7") (pintype "passive"))
      (node (ref "U3") (pin "8") (pinfunction "S_8") (pintype "passive"))
      (node (ref "U7") (pin "8") (pinfunction "VCC_8") (pintype "power_in"))
    )
    (net (code "5") (name "/AC1") (class "Default")
      (node (ref "BR1") (pin "3") (pinfunction "C_3") (pintype "passive"))
    )
    (net (code "6") (name "/AC2") (class "Default")
      (node (ref "BR1") (pin "4") (pinfunction "C_4") (pintype "passive"))
    )
    (net (code "7") (name "/Bat +V") (class "Default")
      (node (ref "R8") (pin "1") (pinfunction "1_1") (pintype "passive"))
      (node (ref "R9") (pin "1") (pinfunction "1_1") (pintype "passive"))
    )
    (net (code "8") (name "/Bat -V") (class "Default")
      (node (ref "D5") (pin "1") (pinfunction "C_1") (pintype "passive"))
    )
    (net (code "9") (name "/RB1") (class "Default")
      (node (ref "C25") (pin "2") (pinfunction "2_2") (pintype "passive"))
      (node (ref "R18") (pin "2") (pinfunction "2_2") (pintype "passive"))
    )
    (net (code "10") (name "/RB2") (class "Default")
      (node (ref "R39") (pin "1") (pinfunction "1_1") (pintype "passive"))
    )
    (net (code "11") (name "/RB3") (class "Default")
      (node (ref "R36") (pin "1") (pinfunction "1_1") (pintype "passive"))
    )
    (net (code "12") (name "/RB4") (class "Default")
      (node (ref "Q5") (pin "3") (pinfunction "C_3") (pintype "passive"))
      (node (ref "R35") (pin "2") (pinfunction "2_2") (pintype "passive"))
    )
    (net (code "13") (name "/RB5") (class "Default")
      (node (ref "Q4") (pin "3") (pinfunction "C_3") (pintype "passive"))
      (node (ref "R32") (pin "2") (pinfunction "2_2") (pintype "passive"))
    )
    (net (code "14") (name "/RE4") (class "Default")
      (node (ref "Q1") (pin "3") (pinfunction "C_3") (pintype "passive"))
      (node (ref "R3") (pin "1") (pinfunction "1_1") (pintype "passive"))
    )
    (net (code "15") (name "/RE9") (class "Default")
      (node (ref "Q3") (pin "3") (pinfunction "C_3") (pintype "passive"))
      (node (ref "R29") (pin "2") (pinfunction "2_2") (pintype "passive"))
    )
    (net (code "16") (name "D+3V3") (class "Default")
      (node (ref "C13") (pin "2") (pinfunction "2_2") (pintype "passive"))
      (node (ref "C14") (pin "2") (pinfunction "2_2") (pintype "passive"))
      (node (ref "U2") (pin "2") (pinfunction "OUT_2") (pintype "power_in"))
      (node (ref "U2") (pin "4") (pinfunction "TAB_4") (pintype "power_in"))
    )
    (net (code "17") (name "D+5") (class "Default")
      (node (ref "C5") (pin "2") (pinfunction "2_2") (pintype "passive"))
      (node (ref "C6") (pin "2") (pinfunction "2_2") (pintype "passive"))
      (node (ref "C7") (pin "2") (pinfunction "2_2") (pintype "passive"))
      (node (ref "C8") (pin "2") (pinfunction "2_2") (pintype "passive"))
      (node (ref "L1") (pin "2") (pinfunction "2_2") (pintype "passive"))
      (node (ref "L2") (pin "1") (pinfunction "1_1") (pintype "passive"))
      (node (ref "L4") (pin "1") (pinfunction "1_1") (pintype "passive"))
      (node (ref "L6") (pin "1") (pinfunction "1_1") (pintype "passive"))
      (node (ref "R5") (pin "2") (pinfunction "2_2") (pintype "passive"))
      (node (ref "R7") (pin "2") (pinfunction "2_2") (pintype "passive"))
    )
    (net (code "18") (name "GND") (class "Default")
      (node (ref "BR1") (pin "2") (pinfunction "A_2") (pintype "passive"))
      (node (ref "C1") (pin "2") (pinfunction "2_2") (pintype "passive"))
      (node (ref "C10") (pin "1") (pinfunction "1_1") (pintype "passive"))
      (node (ref "C11") (pin "1") (pinfunction "1_1") (pintype "passive"))
      (node (ref "C12") (pin "1") (pinfunction "1_1") (pintype "passive"))
      (node (ref "C13") (pin "1") (pinfunction "1_1") (pintype "passive"))
      (node (ref "C14") (pin "1") (pinfunction "1_1") (pintype "passive"))
      (node (ref "C15") (pin "2") (pinfunction "2_2") (pintype "passive"))
      (node (ref "C16") (pin "1") (pinfunction "1_1") (pintype "passive"))
      (node (ref "C17") (pin "1") (pinfunction "1_1") (pintype "passive"))
      (node (ref "C18") (pin "1") (pinfunction "1_1") (pintype "passive"))
      (node (ref "C19") (pin "2") (pinfunction "2_2") (pintype "passive"))
      (node (ref "C2") (pin "2") (pinfunction "2_2") (pintype "passive"))
      (node (ref "C20") (pin "1") (pinfunction "1_1") (pintype "passive"))
      (node (ref "C21") (pin "1") (pinfunction "1_1") (pintype "passive"))
      (node (ref "C22") (pin "1") (pinfunction "1_1") (pintype "passive"))
      (node (ref "C23") (pin "1") (pinfunction "1_1") (pintype "passive"))
      (node (ref "C24") (pin "1") (pinfunction "1_1") (pintype "passive"))
      (node (ref "C25") (pin "1") (pinfunction "1_1") (pintype "passive"))
      (node (ref "C3") (pin "1") (pinfunction "1_1") (pintype "passive"))
      (node (ref "C31") (pin "1") (pinfunction "1_1") (pintype "passive"))
      (node (ref "C5") (pin "1") (pinfunction "1_1") (pintype "passive"))
      (node (ref "C6") (pin "1") (pinfunction "1_1") (pintype "passive"))
      (node (ref "C7") (pin "1") (pinfunction "1_1") (pintype "passive"))
      (node (ref "C8") (pin "1") (pinfunction "1_1") (pintype "passive"))
      (node (ref "C9") (pin "2") (pinfunction "2_2") (pintype "passive"))
      (node (ref "D4") (pin "1") (pinfunction "A_1") (pintype "passive"))
      (node (ref "D9") (pin "3") (pinfunction "A_3") (pintype "passive"))
      (node (ref "LED1") (pin "1") (pinfunction "K_1") (pintype "passive"))
      (node (ref "Q1") (pin "2") (pinfunction "E_2") (pintype "passive"))
      (node (ref "Q2") (pin "1") (pinfunction "LED_CATHODE_1") (pintype "passive"))
      (node (ref "Q2") (pin "6") (pinfunction "PD2_CATHODE_6") (pintype "passive"))
      (node (ref "Q3") (pin "2") (pinfunction "E_2") (pintype "passive"))
      (node (ref "Q4") (pin "2") (pinfunction "E_2") (pintype "passive"))
      (node (ref "Q5") (pin "2") (pinfunction "E_2") (pintype "passive"))
      (node (ref "Q6") (pin "2") (pinfunction "E_2") (pintype "passive"))
      (node (ref "Q7") (pin "2") (pinfunction "E_2") (pintype "passive"))
      (node (ref "R12") (pin "1") (pinfunction "1_1") (pintype "passive"))
      (node (ref "R13") (pin "2") (pinfunction "2_2") (pintype "passive"))
      (node (ref "R17") (pin "2") (pinfunction "2_2") (pintype "passive"))
      (node (ref "R2") (pin "1") (pinfunction "1_1") (pintype "passive"))
      (node (ref "R24") (pin "2") (pinfunction "2_2") (pintype "passive"))
      (node (ref "R28") (pin "2") (pinfunction "2_2") (pintype "passive"))
      (node (ref "R31") (pin "2") (pinfunction "2_2") (pintype "passive"))
      (node (ref "R34") (pin "2") (pinfunction "2_2") (pintype "passive"))
      (node (ref "R37") (pin "2") (pinfunction "2_2") (pintype "passive"))
      (node (ref "R4") (pin "1") (pinfunction "1_1") (pintype "passive"))
      (node (ref "R40") (pin "2") (pinfunction "2_2") (pintype "passive"))
      (node (ref "R6") (pin "1") (pinfunction "1_1") (pintype "passive"))
      (node (ref "U1") (pin "3") (pinfunction "INH_3") (pintype "input"))
      (node (ref "U1") (pin "7") (pinfunction "GND_7") (pintype "power_in"))
      (node (ref "U1") (pin "9") (pinfunction "Thermal_Pad_9") (pintype "power_in"))
      (node (ref "U2") (pin "1") (pinfunction "GND_1") (pintype "power_in"))
      (node (ref "U7") (pin "4") (pinfunction "GND_4") (pintype "power_in"))
      (node (ref "U8") (pin "4") (pinfunction "VSS_4") (pintype "power_in"))
    )
    (net (code "19") (name "LEM+5") (class "Default")
      (node (ref "C15") (pin "1") (pinfunction "1_1") (pintype "passive"))
      (node (ref "C16") (pin "2") (pinfunction "2_2") (pintype "passive"))
      (node (ref "C17") (pin "2") (pinfunction "2_2") (pintype "passive"))
      (node (ref "C18") (pin "2") (pinfunction "2_2") (pintype "passive"))
      (node (ref "L6") (pin "2") (pinfunction "2_2") (pintype "passive"))
    )
    (net (code "20") (name "Net-(BR1-K)") (class "Default")
      (node (ref "BR1") (pin "1") (pinfunction "K_1") (pintype "passive"))
      (node (ref "C1") (pin "1") (pinfunction "1_1") (pintype "passive"))
      (node (ref "D1") (pin "2") (pinfunction "A_2") (pintype "passive"))
      (node (ref "D2") (pin "3") (pinfunction "K_3") (pintype "passive"))
    )
    (net (code "21") (name "Net-(C4-Pad1)") (class "Default")
      (node (ref "C4") (pin "1") (pinfunction "1_1") (pintype "passive"))
      (node (ref "R4") (pin "2") (pinfunction "2_2") (pintype "passive"))
    )
    (net (code "22") (name "Net-(C31-Pad2)") (class "Default")
      (node (ref "C31") (pin "2") (pinfunction "2_2") (pintype "passive"))
      (node (ref "R25") (pin "1") (pinfunction "1_1") (pintype "passive"))
    )
    (net (code "23") (name "Net-(D1-C)") (class "Default")
      (node (ref "C2") (pin "1") (pinfunction "1_1") (pintype "passive"))
      (node (ref "D1") (pin "1") (pinfunction "C_1") (pintype "passive"))
      (node (ref "D3") (pin "1") (pinfunction "C_1") (pintype "passive"))
      (node (ref "U1") (pin "8") (pinfunction "VCC_8") (pintype "power_in"))
    )
    (net (code "24") (name "Net-(D2A-A)") (class "Default")
      (node (ref "D2") (pin "1") (pinfunction "A_1") (pintype "passive"))
      (node (ref "R1") (pin "2") (pinfunction "2_2") (pintype "passive"))
    )
    (net (code "25") (name "Net-(D4-K)") (class "Default")
      (node (ref "D4") (pin "2") (pinfunction "K_2") (pintype "passive"))
      (node (ref "L1") (pin "1") (pinfunction "1_1") (pintype "passive"))
      (node (ref "U1") (pin "1") (pinfunction "OUT_1") (pintype "power_in"))
    )
    (net (code "26") (name "Net-(D5-A)") (class "Default")
      (node (ref "C26") (pin "2") (pinfunction "2_2") (pintype "passive"))
      (node (ref "C27") (pin "2") (pinfunction "2_2") (pintype "passive"))
      (node (ref "C30") (pin "2") (pinfunction "2_2") (pintype "passive"))
      (node (ref "D5") (pin "2") (pinfunction "A_2") (pintype "passive"))
      (node (ref "D8") (pin "2") (pinfunction "A_2") (pintype "passive"))
      (node (ref "R21") (pin "1") (pinfunction "1_1") (pintype "passive"))
    )
    (net (code "27") (name "Net-(D6-A)") (class "Default")
      (node (ref "D6") (pin "2") (pinfunction "A_2") (pintype "passive"))
      (node (ref "R8") (pin "2") (pinfunction "2_2") (pintype "passive"))
    )
    (net (code "28") (name "Net-(D6-C)") (class "Default")
      (node (ref "C26") (pin "1") (pinfunction "1_1") (pintype "passive"))
      (node (ref "D6") (pin "1") (pinfunction "C_1") (pintype "passive"))
      (node (ref "L5") (pin "1") (pinfunction "1_1") (pintype "passive"))
    )
    (net (code "29") (name "Net-(D7-C)") (class "Default")
      (node (ref "C29") (pin "1") (pinfunction "1_1") (pintype "passive"))
      (node (ref "D7") (pin "1") (pinfunction "C_1") (pintype "passive"))
      (node (ref "R20") (pin "2") (pinfunction "2_2") (pintype "passive"))
    )
    (net (code "30") (name "Net-(D10-A1)") (class "Default")
      (node (ref "D10") (pin "1") (pinfunction "A1_1") (pintype "passive"))
      (node (ref "D9") (pin "1") (pinfunction "K1_1") (pintype "passive"))
      (node (ref "R23") (pin "1") (pinfunction "1_1") (pintype "passive"))
      (node (ref "R24") (pin "1") (pinfunction "1_1") (pintype "passive"))
      (node (ref "U8") (pin "5") (pinfunction "VINB+_5") (pintype "input"))
    )
    (net (code "31") (name "Net-(D10-A2)") (class "Default")
      (node (ref "D10") (pin "2") (pinfunction "A2_2") (pintype "passive"))
      (node (ref "D9") (pin "2") (pinfunction "K2_2") (pintype "passive"))
      (node (ref "R22") (pin "1") (pinfunction "1_1") (pintype "passive"))
      (node (ref "R26") (pin "1") (pinfunction "1_1") (pintype "passive"))
      (node (ref "U8") (pin "6") (pinfunction "VINB-_6") (pintype "input"))
    )
    (net (code "32") (name "Net-(D11-C)") (class "Default")
      (node (ref "D11") (pin "1") (pinfunction "C_1") (pintype "passive"))
      (node (ref "R42") (pin "2") (pinfunction "2_2") (pintype "passive"))
    )
    (net (code "33") (name "Net-(LED1-A)") (class "Default")
      (node (ref "LED1") (pin "2") (pinfunction "A_2") (pintype "passive"))
      (node (ref "R7") (pin "1") (pinfunction "1_1") (pintype "passive"))
    )
    (net (code "34") (name "Net-(Q1-B)") (class "Default")
      (node (ref "Q1") (pin "1") (pinfunction "B_1") (pintype "passive"))
      (node (ref "R1") (pin "1") (pinfunction "1_1") (pintype "passive"))
      (node (ref "R2") (pin "2") (pinfunction "2_2") (pintype "passive"))
    )
    (net (code "35") (name "Net-(Q2-LED_ANODE)") (class "Default")
      (node (ref "Q2") (pin "2") (pinfunction "LED_ANODE_2") (pintype "passive"))
      (node (ref "R14") (pin "2") (pinfunction "2_2") (pintype "passive"))
    )
    (net (code "36") (name "Net-(Q2-PD1_ANODE)") (class "Default")
      (node (ref "Q2") (pin "4") (pinfunction "PD1_ANODE_4") (pintype "passive"))
      (node (ref "R13") (pin "1") (pinfunction "1_1") (pintype "passive"))
      (node (ref "U7") (pin "2") (pinfunction "1IN-_2") (pintype "input"))
    )
    (net (code "37") (name "Net-(Q2-PD2_ANODE)") (class "Default")
      (node (ref "Q2") (pin "5") (pinfunction "PD2_ANODE_5") (pintype "passive"))
      (node (ref "R15") (pin "2") (pinfunction "2_2") (pintype "passive"))
    )
    (net (code "38") (name "Net-(Q3-B)") (class "Default")
      (node (ref "Q3") (pin "1") (pinfunction "B_1") (pintype "passive"))
      (node (ref "R27") (pin "1") (pinfunction "1_1") (pintype "passive"))
      (node (ref "R28") (pin "1") (pinfunction "1_1") (pintype "passive"))
    )
    (net (code "39") (name "Net-(Q4-B)") (class "Default")
      (node (ref "Q4") (pin "1") (pinfunction "B_1") (pintype "passive"))
      (node (ref "R30") (pin "1") (pinfunction "1_1") (pintype "passive"))
      (node (ref "R31") (pin "1") (pinfunction "1_1") (pintype "passive"))
    )
    (net (code "40") (name "Net-(Q5-B)") (class "Default")
      (node (ref "Q5") (pin "1") (pinfunction "B_1") (pintype "passive"))
      (node (ref "R33") (pin "1") (pinfunction "1_1") (pintype "passive"))
      (node (ref "R34") (pin "1") (pinfunction "1_1") (pintype "passive"))
    )
    (net (code "41") (name "Net-(Q6-B)") (class "Default")
      (node (ref "Q6") (pin "1") (pinfunction "B_1") (pintype "passive"))
      (node (ref "R36") (pin "2") (pinfunction "2_2") (pintype "passive"))
      (node (ref "R37") (pin "1") (pinfunction "1_1") (pintype "passive"))
    )
    (net (code "42") (name "Net-(Q6-C)") (class "Default")
      (node (ref "Q6") (pin "3") (pinfunction "C_3") (pintype "passive"))
      (node (ref "R38") (pin "1") (pinfunction "1_1") (pintype "passive"))
    )
    (net (code "43") (name "Net-(Q7-B)") (class "Default")
      (node (ref "Q7") (pin "1") (pinfunction "B_1") (pintype "passive"))
      (node (ref "R39") (pin "2") (pinfunction "2_2") (pintype "passive"))
      (node (ref "R40") (pin "1") (pinfunction "1_1") (pintype "passive"))
    )
    (net (code "44") (name "Net-(Q7-C)") (class "Default")
      (node (ref "Q7") (pin "3") (pinfunction "C_3") (pintype "passive"))
      (node (ref "R41") (pin "1") (pinfunction "1_1") (pintype "passive"))
    )
    (net (code "45") (name "Net-(R10-Pad1)") (class "Default")
      (node (ref "R10") (pin "1") (pinfunction "1_1") (pintype "passive"))
      (node (ref "R9") (pin "2") (pinfunction "2_2") (pintype "passive"))
    )
    (net (code "46") (name "Net-(R10-Pad2)") (class "Default")
      (node (ref "R10") (pin "2") (pinfunction "2_2") (pintype "passive"))
      (node (ref "R11") (pin "2") (pinfunction "2_2") (pintype "passive"))
    )
    (net (code "47") (name "Net-(R15-Pad1)") (class "Default")
      (node (ref "R15") (pin "1") (pinfunction "1_1") (pintype "passive"))
      (node (ref "R16") (pin "3") (pinfunction "3_3") (pintype "passive"))
    )
    (net (code "48") (name "Net-(R16-Pad1)") (class "Default")
      (node (ref "R16") (pin "1") (pinfunction "1_1") (pintype "passive"))
      (node (ref "R17") (pin "1") (pinfunction "1_1") (pintype "passive"))
    )
    (net (code "49") (name "Net-(U1-COMP)") (class "Default")
      (node (ref "C3") (pin "2") (pinfunction "2_2") (pintype "passive"))
      (node (ref "C4") (pin "2") (pinfunction "2_2") (pintype "passive"))
      (node (ref "U1") (pin "4") (pinfunction "COMP_4") (pintype "output"))
    )
    (net (code "50") (name "Net-(U1-FB)") (class "Default")
      (node (ref "R5") (pin "1") (pinfunction "1_1") (pintype "passive"))
      (node (ref "R6") (pin "2") (pinfunction "2_2") (pintype "passive"))
      (node (ref "U1") (pin "5") (pinfunction "FB_5") (pintype "input"))
    )
    (net (code "51") (name "Net-(U2-IN)") (class "Default")
      (node (ref "C10") (pin "2") (pinfunction "2_2") (pintype "passive"))
      (node (ref "C11") (pin "2") (pinfunction "2_2") (pintype "passive"))
      (node (ref "C12") (pin "2") (pinfunction "2_2") (pintype "passive"))
      (node (ref "C9") (pin "1") (pinfunction "1_1") (pintype "passive"))
      (node (ref "L2") (pin "2") (pinfunction "2_2") (pintype "passive"))
      (node (ref "U2") (pin "3") (pinfunction "IN_3") (pintype "power_in"))
    )
    (net (code "52") (name "Net-(U3-BP)") (class "Default")
      (node (ref "C28") (pin "2") (pinfunction "2_2") (pintype "passive"))
      (node (ref "U3") (pin "3") (pinfunction "BP_3") (pintype "passive"))
    )
    (net (code "53") (name "Net-(U3-D)") (class "Default")
      (node (ref "C27") (pin "1") (pinfunction "1_1") (pintype "passive"))
      (node (ref "L5") (pin "2") (pinfunction "2_2") (pintype "passive"))
      (node (ref "U3") (pin "5") (pinfunction "D_5") (pintype "passive"))
    )
    (net (code "54") (name "Net-(U3-FB)") (class "Default")
      (node (ref "R19") (pin "2") (pinfunction "2_2") (pintype "passive"))
      (node (ref "R20") (pin "1") (pinfunction "1_1") (pintype "passive"))
      (node (ref "U3") (pin "4") (pinfunction "FB_4") (pintype "passive"))
    )
    (net (code "55") (name "Net-(U7A-1IN+)") (class "Default")
      (node (ref "C23") (pin "2") (pinfunction "2_2") (pintype "passive"))
      (node (ref "R11") (pin "1") (pinfunction "1_1") (pintype "passive"))
      (node (ref "R12") (pin "2") (pinfunction "2_2") (pintype "passive"))
      (node (ref "U7") (pin "3") (pinfunction "1IN+_3") (pintype "input"))
    )
    (net (code "56") (name "Net-(U7A-1OUT)") (class "Default")
      (node (ref "R14") (pin "1") (pinfunction "1_1") (pintype "passive"))
      (node (ref "U7") (pin "1") (pinfunction "1OUT_1") (pintype "output"))
    )
    (net (code "57") (name "Net-(U8A-VINA+)") (class "Default")
      (node (ref "C24") (pin "2") (pinfunction "2_2") (pintype "passive"))
      (node (ref "R16") (pin "2") (pinfunction "2_2") (pintype "passive"))
      (node (ref "U8") (pin "3") (pinfunction "VINA+_3") (pintype "input"))
    )
    (net (code "58") (name "Net-(U8A-VINA-)") (class "Default")
      (node (ref "R18") (pin "1") (pinfunction "1_1") (pintype "passive"))
      (node (ref "U8") (pin "1") (pinfunction "VOUTA_1") (pintype "output"))
      (node (ref "U8") (pin "2") (pinfunction "VINA-_2") (pintype "input"))
    )
    (net (code "59") (name "Net-(U8B-VOUTB)") (class "Default")
      (node (ref "R25") (pin "2") (pinfunction "2_2") (pintype "passive"))
      (node (ref "R26") (pin "2") (pinfunction "2_2") (pintype "passive"))
      (node (ref "U8") (pin "7") (pinfunction "VOUTB_7") (pintype "output"))
    )
    (net (code "60") (name "W+3V3") (class "Default")
      (node (ref "C19") (pin "1") (pinfunction "1_1") (pintype "passive"))
      (node (ref "C20") (pin "2") (pinfunction "2_2") (pintype "passive"))
      (node (ref "C21") (pin "2") (pinfunction "2_2") (pintype "passive"))
      (node (ref "C22") (pin "2") (pinfunction "2_2") (pintype "passive"))
      (node (ref "L4") (pin "2") (pinfunction "2_2") (pintype "passive"))
    )
    (net (code "61") (name "unconnected-(C100-Pad1)") (class "Default")
      (node (ref "C100") (pin "1") (pinfunction "1_1") (pintype "passive"))
    )
    (net (code "62") (name "unconnected-(C100-Pad2)") (class "Default")
      (node (ref "C100") (pin "2") (pinfunction "2_2") (pintype "passive"))
    )
    (net (code "63") (name "unconnected-(C101-Pad1)") (class "Default")
      (node (ref "C101") (pin "1") (pinfunction "1_1") (pintype "passive"))
    )
    (net (code "64") (name "unconnected-(C101-Pad2)") (class "Default")
      (node (ref "C101") (pin "2") (pinfunction "2_2") (pintype "passive"))
    )
    (net (code "65") (name "unconnected-(C102-Pad1)") (class "Default")
      (node (ref "C102") (pin "1") (pinfunction "1_1") (pintype "passive"))
    )
    (net (code "66") (name "unconnected-(C102-Pad2)") (class "Default")
      (node (ref "C102") (pin "2") (pinfunction "2_2") (pintype "passive"))
    )
    (net (code "67") (name "unconnected-(C103-Pad1)") (class "Default")
      (node (ref "C103") (pin "1") (pinfunction "1_1") (pintype "passive"))
    )
    (net (code "68") (name "unconnected-(C103-Pad2)") (class "Default")
      (node (ref "C103") (pin "2") (pinfunction "2_2") (pintype "passive"))
    )
    (net (code "69") (name "unconnected-(C104-Pad1)") (class "Default")
      (node (ref "C104") (pin "1") (pinfunction "1_1") (pintype "passive"))
    )
    (net (code "70") (name "unconnected-(C104-Pad2)") (class "Default")
      (node (ref "C104") (pin "2") (pinfunction "2_2") (pintype "passive"))
    )
    (net (code "71") (name "unconnected-(D2B-NC-Pad2)") (class "Default")
      (node (ref "D2") (pin "2") (pinfunction "NC_2") (pintype "passive"))
    )
    (net (code "72") (name "unconnected-(D12-A-Pad2)") (class "Default")
      (node (ref "D12") (pin "2") (pinfunction "A_2") (pintype "passive"))
    )
    (net (code "73") (name "unconnected-(D12-C-Pad1)") (class "Default")
      (node (ref "D12") (pin "1") (pinfunction "C_1") (pintype "passive"))
    )
    (net (code "74") (name "unconnected-(P2-Pad1)") (class "Default")
      (node (ref "P2") (pin "1") (pinfunction "1_1") (pintype "passive"))
    )
    (net (code "75") (name "unconnected-(P2-Pad2)") (class "Default")
      (node (ref "P2") (pin "2") (pinfunction "2_2") (pintype "passive"))
    )
    (net (code "76") (name "unconnected-(P2-Pad3)") (class "Default")
      (node (ref "P2") (pin "3") (pinfunction "3_3") (pintype "passive"))
    )
    (net (code "77") (name "unconnected-(P2-Pad4)") (class "Default")
      (node (ref "P2") (pin "4") (pinfunction "4_4") (pintype "passive"))
    )
    (net (code "78") (name "unconnected-(P2-Pad5)") (class "Default")
      (node (ref "P2") (pin "5") (pinfunction "5_5") (pintype "passive"))
    )
    (net (code "79") (name "unconnected-(P2-Pad6)") (class "Default")
      (node (ref "P2") (pin "6") (pinfunction "6_6") (pintype "passive"))
    )
    (net (code "80") (name "unconnected-(P2-Pad7)") (class "Default")
      (node (ref "P2") (pin "7") (pinfunction "7_7") (pintype "passive"))
    )
    (net (code "81") (name "unconnected-(P2-Pad8)") (class "Default")
      (node (ref "P2") (pin "8") (pinfunction "8_8") (pintype "passive"))
    )
    (net (code "82") (name "unconnected-(P2-Pad9)") (class "Default")
      (node (ref "P2") (pin "9") (pinfunction "9_9") (pintype "passive"))
    )
    (net (code "83") (name "unconnected-(P2-Pad10)") (class "Default")
      (node (ref "P2") (pin "10") (pinfunction "10_10") (pintype "passive"))
    )
    (net (code "84") (name "unconnected-(P2-Pad11)") (class "Default")
      (node (ref "P2") (pin "11") (pinfunction "11_11") (pintype "passive"))
    )
    (net (code "85") (name "unconnected-(P2-Pad12)") (class "Default")
      (node (ref "P2") (pin "12") (pinfunction "12_12") (pintype "passive"))
    )
    (net (code "86") (name "unconnected-(P2-Pad13)") (class "Default")
      (node (ref "P2") (pin "13") (pinfunction "13_13") (pintype "passive"))
    )
    (net (code "87") (name "unconnected-(P2-Pad14)") (class "Default")
      (node (ref "P2") (pin "14") (pinfunction "14_14") (pintype "passive"))
    )
    (net (code "88") (name "unconnected-(P2-Pad15)") (class "Default")
      (node (ref "P2") (pin "15") (pinfunction "15_15") (pintype "passive"))
    )
    (net (code "89") (name "unconnected-(P2-Pad16)") (class "Default")
      (node (ref "P2") (pin "16") (pinfunction "16_16") (pintype "passive"))
    )
    (net (code "90") (name "unconnected-(P2-Pad17)") (class "Default")
      (node (ref "P2") (pin "17") (pinfunction "17_17") (pintype "passive"))
    )
    (net (code "91") (name "unconnected-(P2-Pad18)") (class "Default")
      (node (ref "P2") (pin "18") (pinfunction "18_18") (pintype "passive"))
    )
    (net (code "92") (name "unconnected-(P2-Pad19)") (class "Default")
      (node (ref "P2") (pin "19") (pinfunction "19_19") (pintype "passive"))
    )
    (net (code "93") (name "unconnected-(P2-Pad20)") (class "Default")
      (node (ref "P2") (pin "20") (pinfunction "20_20") (pintype "passive"))
    )
    (net (code "94") (name "unconnected-(P2-Pad21)") (class "Default")
      (node (ref "P2") (pin "21") (pinfunction "21_21") (pintype "passive"))
    )
    (net (code "95") (name "unconnected-(P2-Pad22)") (class "Default")
      (node (ref "P2") (pin "22") (pinfunction "22_22") (pintype "passive"))
    )
    (net (code "96") (name "unconnected-(P2-Pad23)") (class "Default")
      (node (ref "P2") (pin "23") (pinfunction "23_23") (pintype "passive"))
    )
    (net (code "97") (name "unconnected-(P2-Pad24)") (class "Default")
      (node (ref "P2") (pin "24") (pinfunction "24_24") (pintype "passive"))
    )
    (net (code "98") (name "unconnected-(P3-Pad1)") (class "Default")
      (node (ref "P3") (pin "1") (pinfunction "1_1") (pintype "passive"))
    )
    (net (code "99") (name "unconnected-(P3-Pad2)") (class "Default")
      (node (ref "P3") (pin "2") (pinfunction "2_2") (pintype "passive"))
    )
    (net (code "100") (name "unconnected-(P3-Pad3)") (class "Default")
      (node (ref "P3") (pin "3") (pinfunction "3_3") (pintype "passive"))
    )
    (net (code "101") (name "unconnected-(P3-Pad4)") (class "Default")
      (node (ref "P3") (pin "4") (pinfunction "4_4") (pintype "passive"))
    )
    (net (code "102") (name "unconnected-(P3-Pad5)") (class "Default")
      (node (ref "P3") (pin "5") (pinfunction "5_5") (pintype "passive"))
    )
    (net (code "103") (name "unconnected-(P3-Pad6)") (class "Default")
      (node (ref "P3") (pin "6") (pinfunction "6_6") (pintype "passive"))
    )
    (net (code "104") (name "unconnected-(P3-Pad7)") (class "Default")
      (node (ref "P3") (pin "7") (pinfunction "7_7") (pintype "passive"))
    )
    (net (code "105") (name "unconnected-(P3-Pad8)") (class "Default")
      (node (ref "P3") (pin "8") (pinfunction "8_8") (pintype "passive"))
    )
    (net (code "106") (name "unconnected-(P3-Pad9)") (class "Default")
      (node (ref "P3") (pin "9") (pinfunction "9_9") (pintype "passive"))
    )
    (net (code "107") (name "unconnected-(P3-Pad10)") (class "Default")
      (node (ref "P3") (pin "10") (pinfunction "10_10") (pintype "passive"))
    )
    (net (code "108") (name "unconnected-(P3-Pad11)") (class "Default")
      (node (ref "P3") (pin "11") (pinfunction "11_11") (pintype "passive"))
    )
    (net (code "109") (name "unconnected-(P3-Pad12)") (class "Default")
      (node (ref "P3") (pin "12") (pinfunction "12_12") (pintype "passive"))
    )
    (net (code "110") (name "unconnected-(P3-Pad13)") (class "Default")
      (node (ref "P3") (pin "13") (pinfunction "13_13") (pintype "passive"))
    )
    (net (code "111") (name "unconnected-(P3-Pad14)") (class "Default")
      (node (ref "P3") (pin "14") (pinfunction "14_14") (pintype "passive"))
    )
    (net (code "112") (name "unconnected-(P3-Pad15)") (class "Default")
      (node (ref "P3") (pin "15") (pinfunction "15_15") (pintype "passive"))
    )
    (net (code "113") (name "unconnected-(P3-Pad16)") (class "Default")
      (node (ref "P3") (pin "16") (pinfunction "16_16") (pintype "passive"))
    )
    (net (code "114") (name "unconnected-(Q2-NC-Pad7)") (class "Default")
      (node (ref "Q2") (pin "7") (pinfunction "NC_7") (pintype "passive"))
    )
    (net (code "115") (name "unconnected-(Q2-NC-Pad8)") (class "Default")
      (node (ref "Q2") (pin "8") (pinfunction "NC_8") (pintype "passive"))
    )
    (net (code "116") (name "unconnected-(R22-Pad2)") (class "Default")
      (node (ref "R22") (pin "2") (pinfunction "2_2") (pintype "passive"))
    )
    (net (code "117") (name "unconnected-(R23-Pad2)") (class "Default")
      (node (ref "R23") (pin "2") (pinfunction "2_2") (pintype "passive"))
    )
    (net (code "118") (name "unconnected-(R27-Pad2)") (class "Default")
      (node (ref "R27") (pin "2") (pinfunction "2_2") (pintype "passive"))
    )
    (net (code "119") (name "unconnected-(R30-Pad2)") (class "Default")
      (node (ref "R30") (pin "2") (pinfunction "2_2") (pintype "passive"))
    )
    (net (code "120") (name "unconnected-(R33-Pad2)") (class "Default")
      (node (ref "R33") (pin "2") (pinfunction "2_2") (pintype "passive"))
    )
    (net (code "121") (name "unconnected-(R38-Pad2)") (class "Default")
      (node (ref "R38") (pin "2") (pinfunction "2_2") (pintype "passive"))
    )
    (net (code "122") (name "unconnected-(R41-Pad2)") (class "Default")
      (node (ref "R41") (pin "2") (pinfunction "2_2") (pintype "passive"))
    )
    (net (code "123") (name "unconnected-(R42-Pad1)") (class "Default")
      (node (ref "R42") (pin "1") (pinfunction "1_1") (pintype "passive"))
    )
    (net (code "124") (name "unconnected-(R150-Pad1)") (class "Default")
      (node (ref "R150") (pin "1") (pinfunction "1_1") (pintype "passive"))
    )
    (net (code "125") (name "unconnected-(R150-Pad2)") (class "Default")
      (node (ref "R150") (pin "2") (pinfunction "2_2") (pintype "passive"))
    )
    (net (code "126") (name "unconnected-(U1-SYNC-Pad2)") (class "Default")
      (node (ref "U1") (pin "2") (pinfunction "SYNC_2") (pintype "passive"))
    )
    (net (code "127") (name "unconnected-(U1-VREF-Pad6)") (class "Default")
      (node (ref "U1") (pin "6") (pinfunction "VREF_6") (pintype "power_in"))
    )
    (net (code "128") (name "unconnected-(U7B-2IN+-Pad5)") (class "Default")
      (node (ref "U7") (pin "5") (pinfunction "2IN+_5") (pintype "input"))
    )
    (net (code "129") (name "unconnected-(U7B-2IN--Pad6)") (class "Default")
      (node (ref "U7") (pin "6") (pinfunction "2IN-_6") (pintype "input"))
    )
    (net (code "130") (name "unconnected-(U7B-2OUT-Pad7)") (class "Default")
      (node (ref "U7") (pin "7") (pinfunction "2OUT_7") (pintype "output"))
    )
    (net (code "131") (name "unconnected-(U7B-GND-Pad4)") (class "Default")
      (node (ref "U7") (pin "4") (pinfunction "GND_4") (pintype "power_in"))
    )
    (net (code "132") (name "unconnected-(U7B-VCC-Pad8)") (class "Default")
      (node (ref "U7") (pin "8") (pinfunction "VCC_8") (pintype "power_in"))
    )
    (net (code "133") (name "unconnected-(U8B-VDD-Pad8)") (class "Default")
      (node (ref "U8") (pin "8") (pinfunction "VDD_8") (pintype "power_in"))
    )
    (net (code "134") (name "unconnected-(U8B-VSS-Pad4)") (class "Default")
      (node (ref "U8") (pin "4") (pinfunction "VSS_4") (pintype "power_in"))
    )
  )
)
